# 1s.net
KiCad netlist of a schematic drawn in EAGLE
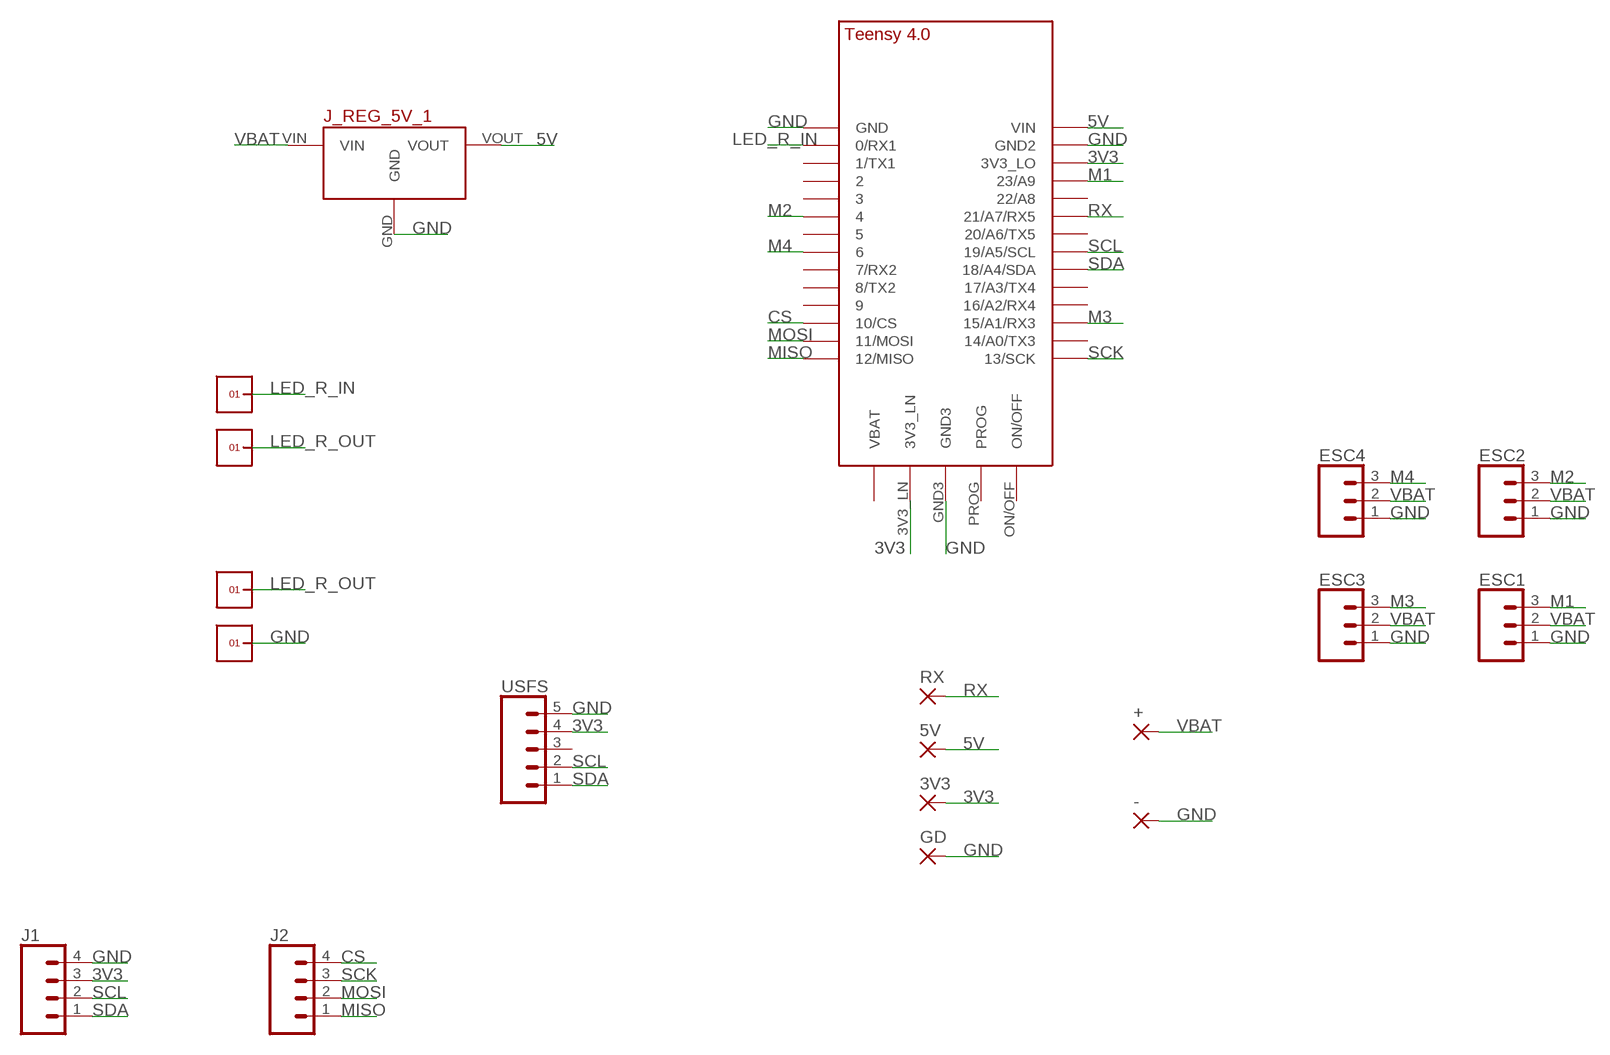
[diagram p0: schematic, sheet 1]

(export (version "E")
  (design (tool "Eeschema 10.0.6"))
  (components
    (comp (ref "+")
      (value "SMD5")
      (footprint "eagle-import:SMD2,54-5,08")
      (libsource (lib "eagle-import") (part "SMD5"))
    )
    (comp (ref "-")
      (value "SMD5")
      (footprint "eagle-import:SMD2,54-5,08")
      (libsource (lib "eagle-import") (part "SMD5"))
    )
    (comp (ref "3V3")
      (value "SMD2")
      (footprint "eagle-import:SMD1,27-2,54")
      (libsource (lib "eagle-import") (part "SMD2"))
    )
    (comp (ref "5V")
      (value "SMD2")
      (footprint "eagle-import:SMD1,27-2,54")
      (libsource (lib "eagle-import") (part "SMD2"))
    )
    (comp (ref "ESC1")
      (value "455-1750-1-ND")
      (footprint "eagle-import:1X03")
      (libsource (lib "eagle-import") (part "CONN_03"))
    )
    (comp (ref "ESC2")
      (value "455-1750-1-ND")
      (footprint "eagle-import:1X03")
      (libsource (lib "eagle-import") (part "CONN_03"))
    )
    (comp (ref "ESC3")
      (value "455-1750-1-ND")
      (footprint "eagle-import:1X03")
      (libsource (lib "eagle-import") (part "CONN_03"))
    )
    (comp (ref "ESC4")
      (value "455-1750-1-ND")
      (footprint "eagle-import:1X03")
      (libsource (lib "eagle-import") (part "CONN_03"))
    )
    (comp (ref "GD")
      (value "SMD2")
      (footprint "eagle-import:SMD1,27-2,54")
      (libsource (lib "eagle-import") (part "SMD2"))
    )
    (comp (ref "J1")
      (value "CONN_041X04_NO_SILK")
      (footprint "eagle-import:1X04_NO_SILK")
      (libsource (lib "eagle-import") (part "CONN_041X04_NO_SILK"))
    )
    (comp (ref "J2")
      (value "CONN_041X04_NO_SILK")
      (footprint "eagle-import:1X04_NO_SILK")
      (libsource (lib "eagle-import") (part "CONN_041X04_NO_SILK"))
    )
    (comp (ref "J_REG_5V_1")
      (value "5V_VOLTAGE_REGULATOR")
      (footprint "eagle-import:5V_VOLTAGE_REGULATOR")
      (libsource (lib "eagle-import") (part "5V_VOLTAGE_REGULATOR"))
    )
    (comp (ref "RX")
      (value "SMD2")
      (footprint "eagle-import:SMD1,27-2,54")
      (libsource (lib "eagle-import") (part "SMD2"))
    )
    (comp (ref "U$1")
      (value "TEENSY_4.0")
      (footprint "eagle-import:TEENSY_4.0")
      (libsource (lib "eagle-import") (part "TEENSY_4.0"))
    )
    (comp (ref "U$3")
      (value "1X1")
      (footprint "eagle-import:1X1")
      (libsource (lib "eagle-import") (part "1X1"))
    )
    (comp (ref "U$4")
      (value "1X1")
      (footprint "eagle-import:1X1")
      (libsource (lib "eagle-import") (part "1X1"))
    )
    (comp (ref "U$6")
      (value "1X1")
      (footprint "eagle-import:1X1")
      (libsource (lib "eagle-import") (part "1X1"))
    )
    (comp (ref "U$7")
      (value "1X1")
      (footprint "eagle-import:1X1")
      (libsource (lib "eagle-import") (part "1X1"))
    )
    (comp (ref "USFS")
      (value "CONN_05NO_SILK")
      (footprint "eagle-import:1X05_NO_SILK")
      (libsource (lib "eagle-import") (part "CONN_05NO_SILK"))
    )
  )
  (nets
    (net (code "1") (name "/3V3") (class "Default")
      (node (ref "3V3") (pin "1") (pinfunction "P_1") (pintype "passive"))
      (node (ref "J1") (pin "3") (pinfunction "3_3") (pintype "passive"))
      (node (ref "U$1") (pin "3V3_LN") (pinfunction "3V3_LN_3V3_LN") (pintype "bidirectional"))
      (node (ref "U$1") (pin "3V3_LO") (pinfunction "3V3_LO_3V3_LO") (pintype "bidirectional"))
      (node (ref "USFS") (pin "4") (pinfunction "4_4") (pintype "passive"))
    )
    (net (code "2") (name "/5V") (class "Default")
      (node (ref "5V") (pin "1") (pinfunction "P_1") (pintype "passive"))
      (node (ref "J_REG_5V_1") (pin "VOUT") (pinfunction "VOUT_VOUT") (pintype "bidirectional"))
      (node (ref "U$1") (pin "VIN") (pinfunction "VIN_VIN") (pintype "bidirectional"))
    )
    (net (code "3") (name "/CS") (class "Default")
      (node (ref "J2") (pin "4") (pinfunction "4_4") (pintype "passive"))
      (node (ref "U$1") (pin "10/CS") (pinfunction "10/CS_10/CS") (pintype "bidirectional"))
    )
    (net (code "4") (name "/GND") (class "Default")
      (node (ref "-") (pin "1") (pinfunction "P_1") (pintype "passive"))
      (node (ref "ESC1") (pin "1") (pinfunction "1_1") (pintype "passive"))
      (node (ref "ESC2") (pin "1") (pinfunction "1_1") (pintype "passive"))
      (node (ref "ESC3") (pin "1") (pinfunction "1_1") (pintype "passive"))
      (node (ref "ESC4") (pin "1") (pinfunction "1_1") (pintype "passive"))
      (node (ref "GD") (pin "1") (pinfunction "P_1") (pintype "passive"))
      (node (ref "J1") (pin "4") (pinfunction "4_4") (pintype "passive"))
      (node (ref "J_REG_5V_1") (pin "GND") (pinfunction "GND_GND") (pintype "bidirectional"))
      (node (ref "U$1") (pin "GND") (pinfunction "GND_GND") (pintype "bidirectional"))
      (node (ref "U$1") (pin "GND2") (pinfunction "GND2_GND2") (pintype "bidirectional"))
      (node (ref "U$1") (pin "GND3") (pinfunction "GND3_GND3") (pintype "bidirectional"))
      (node (ref "U$7") (pin "1") (pinfunction "1_1") (pintype "bidirectional"))
      (node (ref "USFS") (pin "5") (pinfunction "5_5") (pintype "passive"))
    )
    (net (code "5") (name "/LED_R_IN") (class "Default")
      (node (ref "U$1") (pin "0/RX") (pinfunction "0/RX1_0/RX") (pintype "bidirectional"))
      (node (ref "U$3") (pin "1") (pinfunction "1_1") (pintype "bidirectional"))
    )
    (net (code "6") (name "/LED_R_OUT") (class "Default")
      (node (ref "U$4") (pin "1") (pinfunction "1_1") (pintype "bidirectional"))
      (node (ref "U$6") (pin "1") (pinfunction "1_1") (pintype "bidirectional"))
    )
    (net (code "7") (name "/M1") (class "Default")
      (node (ref "ESC1") (pin "3") (pinfunction "3_3") (pintype "passive"))
      (node (ref "U$1") (pin "23/A9") (pinfunction "23/A9_23/A9") (pintype "bidirectional"))
    )
    (net (code "8") (name "/M2") (class "Default")
      (node (ref "ESC2") (pin "3") (pinfunction "3_3") (pintype "passive"))
      (node (ref "U$1") (pin "4/CANRX") (pinfunction "4_4/CANRX") (pintype "bidirectional"))
    )
    (net (code "9") (name "/M3") (class "Default")
      (node (ref "ESC3") (pin "3") (pinfunction "3_3") (pintype "passive"))
      (node (ref "U$1") (pin "15/A1") (pinfunction "15/A1/RX3_15/A1") (pintype "bidirectional"))
    )
    (net (code "10") (name "/M4") (class "Default")
      (node (ref "ESC4") (pin "3") (pinfunction "3_3") (pintype "passive"))
      (node (ref "U$1") (pin "6") (pinfunction "6_6") (pintype "bidirectional"))
    )
    (net (code "11") (name "/MISO") (class "Default")
      (node (ref "J2") (pin "1") (pinfunction "1_1") (pintype "passive"))
      (node (ref "U$1") (pin "12/MISO") (pinfunction "12/MISO_12/MISO") (pintype "bidirectional"))
    )
    (net (code "12") (name "/MOSI") (class "Default")
      (node (ref "J2") (pin "2") (pinfunction "2_2") (pintype "passive"))
      (node (ref "U$1") (pin "11/MOSI") (pinfunction "11/MOSI_11/MOSI") (pintype "bidirectional"))
    )
    (net (code "13") (name "/RX") (class "Default")
      (node (ref "RX") (pin "1") (pinfunction "P_1") (pintype "passive"))
      (node (ref "U$1") (pin "21/A7") (pinfunction "21/A7/RX5_21/A7") (pintype "bidirectional"))
    )
    (net (code "14") (name "/SCK") (class "Default")
      (node (ref "J2") (pin "3") (pinfunction "3_3") (pintype "passive"))
      (node (ref "U$1") (pin "13/SCK") (pinfunction "13/SCK_13/SCK") (pintype "bidirectional"))
    )
    (net (code "15") (name "/SCL") (class "Default")
      (node (ref "J1") (pin "2") (pinfunction "2_2") (pintype "passive"))
      (node (ref "U$1") (pin "19/A5/SCL") (pinfunction "19/A5/SCL_19/A5/SCL") (pintype "bidirectional"))
      (node (ref "USFS") (pin "2") (pinfunction "2_2") (pintype "passive"))
    )
    (net (code "16") (name "/SDA") (class "Default")
      (node (ref "J1") (pin "1") (pinfunction "1_1") (pintype "passive"))
      (node (ref "U$1") (pin "18/A4/SDA") (pinfunction "18/A4/SDA_18/A4/SDA") (pintype "bidirectional"))
      (node (ref "USFS") (pin "1") (pinfunction "1_1") (pintype "passive"))
    )
    (net (code "17") (name "/VBAT") (class "Default")
      (node (ref "+") (pin "1") (pinfunction "P_1") (pintype "passive"))
      (node (ref "ESC1") (pin "2") (pinfunction "2_2") (pintype "passive"))
      (node (ref "ESC2") (pin "2") (pinfunction "2_2") (pintype "passive"))
      (node (ref "ESC3") (pin "2") (pinfunction "2_2") (pintype "passive"))
      (node (ref "ESC4") (pin "2") (pinfunction "2_2") (pintype "passive"))
      (node (ref "J_REG_5V_1") (pin "VIN") (pinfunction "VIN_VIN") (pintype "bidirectional"))
    )
    (net (code "18") (name "unconnected-(U$1-1{slash}TX1-Pad1{slash}TX)") (class "Default")
      (node (ref "U$1") (pin "1/TX") (pinfunction "1/TX1_1/TX") (pintype "bidirectional"))
    )
    (net (code "19") (name "unconnected-(U$1-3-Pad3{slash}CANTX)") (class "Default")
      (node (ref "U$1") (pin "3/CANTX") (pinfunction "3_3/CANTX") (pintype "bidirectional"))
    )
    (net (code "20") (name "unconnected-(U$1-7{slash}RX2-Pad7)") (class "Default")
      (node (ref "U$1") (pin "7") (pinfunction "7/RX2_7") (pintype "bidirectional"))
    )
    (net (code "21") (name "unconnected-(U$1-8{slash}TX2-Pad8)") (class "Default")
      (node (ref "U$1") (pin "8") (pinfunction "8/TX2_8") (pintype "bidirectional"))
    )
    (net (code "22") (name "unconnected-(U$1-9-Pad9{slash}CS)") (class "Default")
      (node (ref "U$1") (pin "9/CS") (pinfunction "9_9/CS") (pintype "bidirectional"))
    )
    (net (code "23") (name "unconnected-(U$1-14{slash}A0{slash}TX3-Pad14{slash}A0)") (class "Default")
      (node (ref "U$1") (pin "14/A0") (pinfunction "14/A0/TX3_14/A0") (pintype "bidirectional"))
    )
    (net (code "24") (name "unconnected-(U$1-16{slash}A2{slash}RX4-Pad16{slash}A2)") (class "Default")
      (node (ref "U$1") (pin "16/A2") (pinfunction "16/A2/RX4_16/A2") (pintype "bidirectional"))
    )
    (net (code "25") (name "unconnected-(U$1-17{slash}A3{slash}TX4-Pad17{slash}A3)") (class "Default")
      (node (ref "U$1") (pin "17/A3") (pinfunction "17/A3/TX4_17/A3") (pintype "bidirectional"))
    )
    (net (code "26") (name "unconnected-(U$1-20{slash}A6{slash}TX5-Pad20{slash}A6)") (class "Default")
      (node (ref "U$1") (pin "20/A6") (pinfunction "20/A6/TX5_20/A6") (pintype "bidirectional"))
    )
    (net (code "27") (name "unconnected-(U$1-Pad2)") (class "Default")
      (node (ref "U$1") (pin "2") (pinfunction "2_2") (pintype "bidirectional"))
    )
    (net (code "28") (name "unconnected-(U$1-Pad5)") (class "Default")
      (node (ref "U$1") (pin "5") (pinfunction "5_5") (pintype "bidirectional"))
    )
    (net (code "29") (name "unconnected-(U$1-Pad22{slash}A8)") (class "Default")
      (node (ref "U$1") (pin "22/A8") (pinfunction "22/A8_22/A8") (pintype "bidirectional"))
    )
    (net (code "30") (name "unconnected-(U$1-PadON{slash}OFF)") (class "Default")
      (node (ref "U$1") (pin "ON/OFF") (pinfunction "ON/OFF_ON/OFF") (pintype "bidirectional"))
    )
    (net (code "31") (name "unconnected-(U$1-PadPROG)") (class "Default")
      (node (ref "U$1") (pin "PROG") (pinfunction "PROG_PROG") (pintype "bidirectional"))
    )
    (net (code "32") (name "unconnected-(U$1-VBAT-PadVBAT\\)") (class "Default")
      (node (ref "U$1") (pin "VBAT\\") (pinfunction "VBAT_VBAT\\") (pintype "bidirectional"))
    )
    (net (code "33") (name "unconnected-(USFS-Pad3)") (class "Default")
      (node (ref "USFS") (pin "3") (pinfunction "3_3") (pintype "passive"))
    )
  )
)
